# OSO-MISC-20-027_AirLift_Adapter_for_Sens.net
KiCad netlist of a schematic drawn in EAGLE
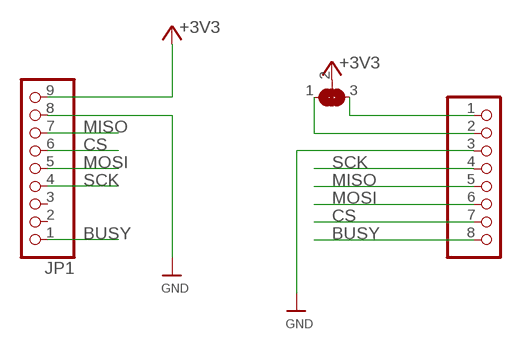
[diagram p0: schematic, sheet 1]

(export (version "E")
  (design (tool "Eeschema 10.0.6"))
  (components
    (comp (ref "JP1")
      (value "HEADER-1X9_JSTSH")
      (footprint "eagle-import:JST_SH9")
      (libsource (lib "eagle-import") (part "HEADER-1X9_JSTSH"))
    )
    (comp (ref "JP2")
      (value "PINHD-1X8/90")
      (footprint "eagle-import:1X08_90")
      (libsource (lib "eagle-import") (part "PINHD-1X8/90"))
    )
    (comp (ref "SJ1")
      (value "SOLDERJUMPER_2WAY")
      (footprint "eagle-import:SOLDERJUMPER_2WAY_OPEN_NOPASTE")
      (libsource (lib "eagle-import") (part "SOLDERJUMPER_2WAY"))
    )
  )
  (nets
    (net (code "1") (name "+3V3") (class "Default")
      (node (ref "JP1") (pin "9") (pinfunction "9_9") (pintype "passive"))
      (node (ref "SJ1") (pin "2") (pinfunction "2_2") (pintype "passive"))
    )
    (net (code "2") (name "/BUSY") (class "Default")
      (node (ref "JP1") (pin "1") (pinfunction "1_1") (pintype "passive"))
      (node (ref "JP2") (pin "8") (pinfunction "8_8") (pintype "passive"))
    )
    (net (code "3") (name "/CS") (class "Default")
      (node (ref "JP1") (pin "6") (pinfunction "6_6") (pintype "passive"))
      (node (ref "JP2") (pin "7") (pinfunction "7_7") (pintype "passive"))
    )
    (net (code "4") (name "/MISO") (class "Default")
      (node (ref "JP1") (pin "7") (pinfunction "7_7") (pintype "passive"))
      (node (ref "JP2") (pin "5") (pinfunction "5_5") (pintype "passive"))
    )
    (net (code "5") (name "/MOSI") (class "Default")
      (node (ref "JP1") (pin "5") (pinfunction "5_5") (pintype "passive"))
      (node (ref "JP2") (pin "6") (pinfunction "6_6") (pintype "passive"))
    )
    (net (code "6") (name "/SCK") (class "Default")
      (node (ref "JP1") (pin "4") (pinfunction "4_4") (pintype "passive"))
      (node (ref "JP2") (pin "4") (pinfunction "4_4") (pintype "passive"))
    )
    (net (code "7") (name "GND") (class "Default")
      (node (ref "JP1") (pin "8") (pinfunction "8_8") (pintype "passive"))
      (node (ref "JP2") (pin "3") (pinfunction "3_3") (pintype "passive"))
    )
    (net (code "8") (name "Net-(JP2-Pad1)") (class "Default")
      (node (ref "JP2") (pin "1") (pinfunction "1_1") (pintype "passive"))
      (node (ref "SJ1") (pin "3") (pinfunction "3_3") (pintype "passive"))
    )
    (net (code "9") (name "Net-(JP2-Pad2)") (class "Default")
      (node (ref "JP2") (pin "2") (pinfunction "2_2") (pintype "passive"))
      (node (ref "SJ1") (pin "1") (pinfunction "1_1") (pintype "passive"))
    )
    (net (code "10") (name "unconnected-(JP1-Pad2)") (class "Default")
      (node (ref "JP1") (pin "2") (pinfunction "2_2") (pintype "passive"))
    )
    (net (code "11") (name "unconnected-(JP1-Pad3)") (class "Default")
      (node (ref "JP1") (pin "3") (pinfunction "3_3") (pintype "passive"))
    )
  )
)
